# IRLED_Board.net
KiCad netlist of a schematic drawn in Altium Designer
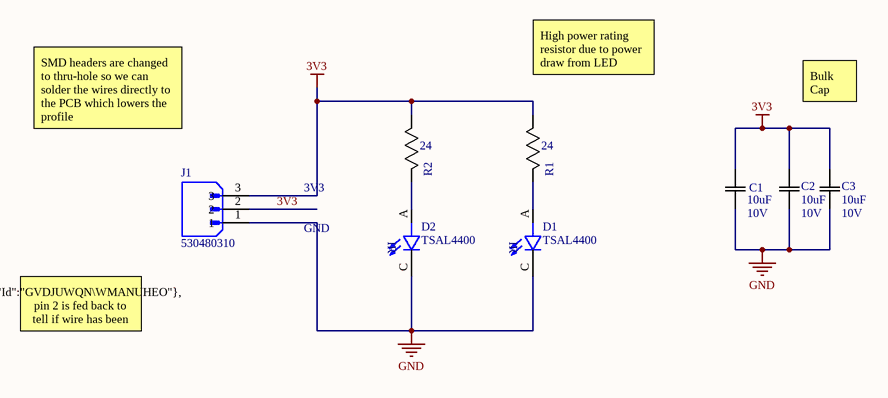
[diagram p0: IRLED Board.SchDoc]

(export (version "E")
  (design (tool "Eeschema 10.0.6"))
  (components
    (comp (ref "C1")
      (value "10uF")
      (footprint "0603")
      (description "Default Symbol for Capacitors")
      (fields
        (field (name "RATING") "10V")
        (field (name "PART NUMBER") "CAP 10uF 10V")
        (field (name "TOLERANCE") "10%")
      )
      (libsource (lib "capacitor_library") (part "CAP_Default"))
    )
    (comp (ref "C2")
      (value "10uF")
      (footprint "0603")
      (description "Default Symbol for Capacitors")
      (fields
        (field (name "RATING") "10V")
        (field (name "PART NUMBER") "CAP 10uF 10V")
        (field (name "TOLERANCE") "10%")
      )
      (libsource (lib "capacitor_library") (part "CAP_Default"))
    )
    (comp (ref "C3")
      (value "10uF")
      (footprint "0603")
      (description "Default Symbol for Capacitors")
      (fields
        (field (name "RATING") "10V")
        (field (name "PART NUMBER") "CAP 10uF 10V")
        (field (name "TOLERANCE") "10%")
      )
      (libsource (lib "capacitor_library") (part "CAP_Default"))
    )
    (comp (ref "D1")
      (value "TSAL4400")
      (footprint "IR940FOOTPRINT")
      (description "Infrared Emitter 940nm 36mW/sr Circular Top Mount 2-Pin T-1 Bulk")
      (fields (field (name "MF") "Vishay Semiconductor"))
      (libsource (lib "Diode_Library") (part "TSAL4400"))
    )
    (comp (ref "D2")
      (value "TSAL4400")
      (footprint "IR940FOOTPRINT")
      (description "Infrared Emitter 940nm 36mW/sr Circular Top Mount 2-Pin T-1 Bulk")
      (fields (field (name "MF") "Vishay Semiconductor"))
      (libsource (lib "Diode_Library") (part "TSAL4400"))
    )
    (comp (ref "J1")
      (value "530480310")
      (footprint "MOLEX_530480310")
      (fields (field (name "PART NUMBER") "HDR 3POS 90deg THRU 1.25mm"))
      (libsource (lib "Connector_Library") (part "530480310"))
    )
    (comp (ref "R1")
      (value "24")
      (footprint "1206")
      (description "Default Resistor Symbol")
      (fields (field (name "TOLERANCE") "0.5%") (field (name "PART NUMBER") "RES 24 1W - 0.5%"))
      (libsource (lib "Resistor_Library") (part "RES_DEFAULT"))
    )
    (comp (ref "R2")
      (value "24")
      (footprint "1206")
      (description "Default Resistor Symbol")
      (fields (field (name "TOLERANCE") "0.5%") (field (name "PART NUMBER") "RES 24 1W - 0.5%"))
      (libsource (lib "Resistor_Library") (part "RES_DEFAULT"))
    )
  )
  (nets
    (net (code "1") (name "3V3") (class "Default")
      (node (ref "C1") (pin "2") (pinfunction "C2_2") (pintype "passive"))
      (node (ref "C2") (pin "2") (pinfunction "C2_2") (pintype "passive"))
      (node (ref "C3") (pin "2") (pinfunction "C2_2") (pintype "passive"))
      (node (ref "J1") (pin "2") (pinfunction "2_2") (pintype "passive"))
      (node (ref "J1") (pin "3") (pinfunction "3_3") (pintype "passive"))
      (node (ref "R1") (pin "1") (pinfunction "R1_1") (pintype "passive"))
      (node (ref "R2") (pin "1") (pinfunction "R1_1") (pintype "passive"))
    )
    (net (code "2") (name "GND") (class "Default")
      (node (ref "C1") (pin "1") (pinfunction "C1_1") (pintype "passive"))
      (node (ref "C2") (pin "1") (pinfunction "C1_1") (pintype "passive"))
      (node (ref "C3") (pin "1") (pinfunction "C1_1") (pintype "passive"))
      (node (ref "D1") (pin "C") (pinfunction "C_C") (pintype "passive"))
      (node (ref "D2") (pin "C") (pinfunction "C_C") (pintype "passive"))
      (node (ref "J1") (pin "1") (pinfunction "1_1") (pintype "passive"))
    )
    (net (code "3") (name "Net-(R1-R2)") (class "Default")
      (node (ref "D1") (pin "A") (pinfunction "A_A") (pintype "passive"))
      (node (ref "R1") (pin "2") (pinfunction "R2_2") (pintype "passive"))
    )
    (net (code "4") (name "Net-(R2-R2)") (class "Default")
      (node (ref "D2") (pin "A") (pinfunction "A_A") (pintype "passive"))
      (node (ref "R2") (pin "2") (pinfunction "R2_2") (pintype "passive"))
    )
  )
)
